# Mosfets.net
KiCad netlist of a schematic drawn in Altium Designer
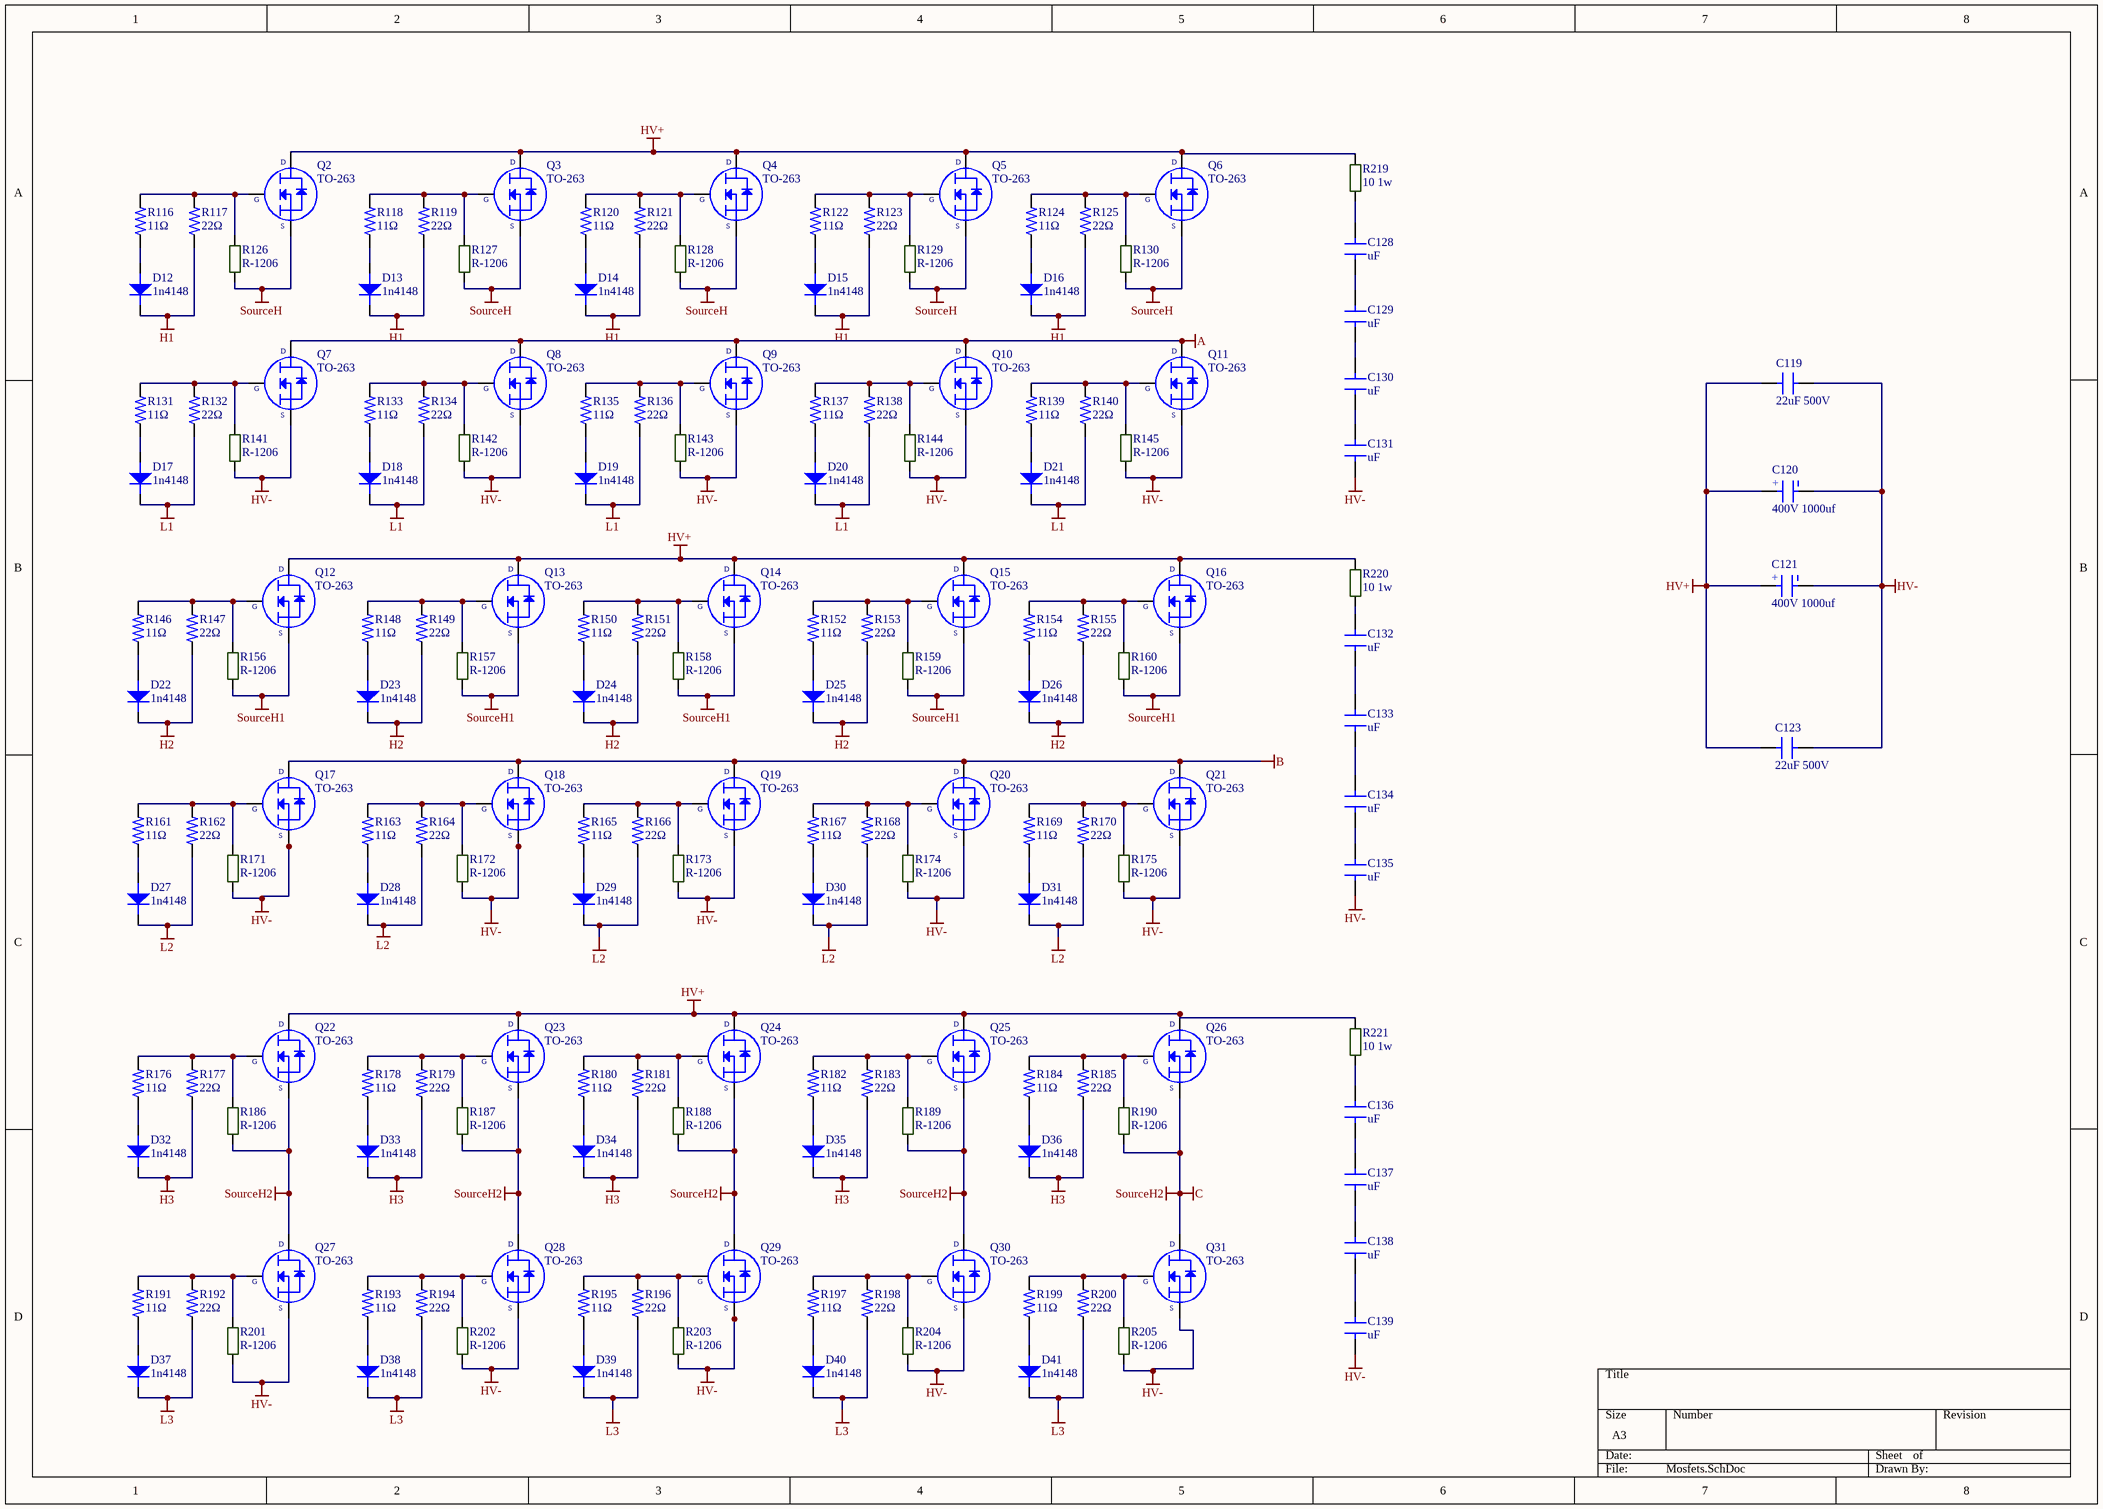
[diagram p0: Mosfets.SchDoc]

(export (version "E")
  (design (tool "Eeschema 10.0.6"))
  (components
    (comp (ref "C119")
      (value "22uF 500V")
      (footprint "CAP.POL 22UF 500VDC - duplicate")
      (libsource (lib "Gate Driver Board") (part "CAP.POL 22UF 500VDC"))
    )
    (comp (ref "C120")
      (value "400V 1000uf")
      (footprint "Koshin 63v 4700 cap")
      (fields
        (field (name "MANUFACTURER") "Nichicon")
        (field (name "MANUFACTURER PART NUMBER") "LKS1J472MESZ")
        (field (name "TOLERANCE") "20%")
      )
      (libsource (lib "Gate Driver Board") (part "Aluminum Electrolytic Capacitors"))
    )
    (comp (ref "C121")
      (value "400V 1000uf")
      (footprint "Koshin 63v 4700 cap")
      (fields
        (field (name "MANUFACTURER") "Nichicon")
        (field (name "MANUFACTURER PART NUMBER") "LKS1J472MESZ")
        (field (name "TOLERANCE") "20%")
      )
      (libsource (lib "Gate Driver Board") (part "Aluminum Electrolytic Capacitors"))
    )
    (comp (ref "C123")
      (value "22uF 500V")
      (footprint "CAP.POL 22UF 500VDC - duplicate")
      (libsource (lib "Gate Driver Board") (part "CAP.POL 22UF 500VDC"))
    )
    (comp (ref "C128")
      (value "uF")
      (footprint "C-1206")
      (libsource (lib "Gate Driver Board") (part "C-1206"))
    )
    (comp (ref "C129")
      (value "uF")
      (footprint "C-1206")
      (libsource (lib "Gate Driver Board") (part "C-1206"))
    )
    (comp (ref "C130")
      (value "uF")
      (footprint "C-1206")
      (libsource (lib "Gate Driver Board") (part "C-1206"))
    )
    (comp (ref "C131")
      (value "uF")
      (footprint "C-1206")
      (libsource (lib "Gate Driver Board") (part "C-1206"))
    )
    (comp (ref "C132")
      (value "uF")
      (footprint "C-1206")
      (libsource (lib "Gate Driver Board") (part "C-1206"))
    )
    (comp (ref "C133")
      (value "uF")
      (footprint "C-1206")
      (libsource (lib "Gate Driver Board") (part "C-1206"))
    )
    (comp (ref "C134")
      (value "uF")
      (footprint "C-1206")
      (libsource (lib "Gate Driver Board") (part "C-1206"))
    )
    (comp (ref "C135")
      (value "uF")
      (footprint "C-1206")
      (libsource (lib "Gate Driver Board") (part "C-1206"))
    )
    (comp (ref "C136")
      (value "uF")
      (footprint "C-1206")
      (libsource (lib "Gate Driver Board") (part "C-1206"))
    )
    (comp (ref "C137")
      (value "uF")
      (footprint "C-1206")
      (libsource (lib "Gate Driver Board") (part "C-1206"))
    )
    (comp (ref "C138")
      (value "uF")
      (footprint "C-1206")
      (libsource (lib "Gate Driver Board") (part "C-1206"))
    )
    (comp (ref "C139")
      (value "uF")
      (footprint "C-1206")
      (libsource (lib "Gate Driver Board") (part "C-1206"))
    )
    (comp (ref "D12")
      (value "1n4148")
      (footprint "LFI Power Board PcbLib1:SOD123")
      (description "Diode Small Signal Switching 100V 0.15A 2-Pin SOD-123 T/R")
      (fields
        (field (name "MANUFACTURER") "Vishay")
        (field (name "MANUFACTURER PART NUMBER") "1N4148W-E3-18")
      )
      (libsource (lib "Gate Driver Board") (part "1N4148W-E3-18"))
    )
    (comp (ref "D13")
      (value "1n4148")
      (footprint "LFI Power Board PcbLib1:SOD123")
      (description "Diode Small Signal Switching 100V 0.15A 2-Pin SOD-123 T/R")
      (fields
        (field (name "MANUFACTURER") "Vishay")
        (field (name "MANUFACTURER PART NUMBER") "1N4148W-E3-18")
      )
      (libsource (lib "Gate Driver Board") (part "1N4148W-E3-18"))
    )
    (comp (ref "D14")
      (value "1n4148")
      (footprint "LFI Power Board PcbLib1:SOD123")
      (description "Diode Small Signal Switching 100V 0.15A 2-Pin SOD-123 T/R")
      (fields
        (field (name "MANUFACTURER") "Vishay")
        (field (name "MANUFACTURER PART NUMBER") "1N4148W-E3-18")
      )
      (libsource (lib "Gate Driver Board") (part "1N4148W-E3-18"))
    )
    (comp (ref "D15")
      (value "1n4148")
      (footprint "LFI Power Board PcbLib1:SOD123")
      (description "Diode Small Signal Switching 100V 0.15A 2-Pin SOD-123 T/R")
      (fields
        (field (name "MANUFACTURER") "Vishay")
        (field (name "MANUFACTURER PART NUMBER") "1N4148W-E3-18")
      )
      (libsource (lib "Gate Driver Board") (part "1N4148W-E3-18"))
    )
    (comp (ref "D16")
      (value "1n4148")
      (footprint "LFI Power Board PcbLib1:SOD123")
      (description "Diode Small Signal Switching 100V 0.15A 2-Pin SOD-123 T/R")
      (fields
        (field (name "MANUFACTURER") "Vishay")
        (field (name "MANUFACTURER PART NUMBER") "1N4148W-E3-18")
      )
      (libsource (lib "Gate Driver Board") (part "1N4148W-E3-18"))
    )
    (comp (ref "D17")
      (value "1n4148")
      (footprint "LFI Power Board PcbLib1:SOD123")
      (description "Diode Small Signal Switching 100V 0.15A 2-Pin SOD-123 T/R")
      (fields
        (field (name "MANUFACTURER") "Vishay")
        (field (name "MANUFACTURER PART NUMBER") "1N4148W-E3-18")
      )
      (libsource (lib "Gate Driver Board") (part "1N4148W-E3-18"))
    )
    (comp (ref "D18")
      (value "1n4148")
      (footprint "LFI Power Board PcbLib1:SOD123")
      (description "Diode Small Signal Switching 100V 0.15A 2-Pin SOD-123 T/R")
      (fields
        (field (name "MANUFACTURER") "Vishay")
        (field (name "MANUFACTURER PART NUMBER") "1N4148W-E3-18")
      )
      (libsource (lib "Gate Driver Board") (part "1N4148W-E3-18"))
    )
    (comp (ref "D19")
      (value "1n4148")
      (footprint "LFI Power Board PcbLib1:SOD123")
      (description "Diode Small Signal Switching 100V 0.15A 2-Pin SOD-123 T/R")
      (fields
        (field (name "MANUFACTURER") "Vishay")
        (field (name "MANUFACTURER PART NUMBER") "1N4148W-E3-18")
      )
      (libsource (lib "Gate Driver Board") (part "1N4148W-E3-18"))
    )
    (comp (ref "D20")
      (value "1n4148")
      (footprint "LFI Power Board PcbLib1:SOD123")
      (description "Diode Small Signal Switching 100V 0.15A 2-Pin SOD-123 T/R")
      (fields
        (field (name "MANUFACTURER") "Vishay")
        (field (name "MANUFACTURER PART NUMBER") "1N4148W-E3-18")
      )
      (libsource (lib "Gate Driver Board") (part "1N4148W-E3-18"))
    )
    (comp (ref "D21")
      (value "1n4148")
      (footprint "LFI Power Board PcbLib1:SOD123")
      (description "Diode Small Signal Switching 100V 0.15A 2-Pin SOD-123 T/R")
      (fields
        (field (name "MANUFACTURER") "Vishay")
        (field (name "MANUFACTURER PART NUMBER") "1N4148W-E3-18")
      )
      (libsource (lib "Gate Driver Board") (part "1N4148W-E3-18"))
    )
    (comp (ref "D22")
      (value "1n4148")
      (footprint "LFI Power Board PcbLib1:SOD123")
      (description "Diode Small Signal Switching 100V 0.15A 2-Pin SOD-123 T/R")
      (fields
        (field (name "MANUFACTURER") "Vishay")
        (field (name "MANUFACTURER PART NUMBER") "1N4148W-E3-18")
      )
      (libsource (lib "Gate Driver Board") (part "1N4148W-E3-18"))
    )
    (comp (ref "D23")
      (value "1n4148")
      (footprint "LFI Power Board PcbLib1:SOD123")
      (description "Diode Small Signal Switching 100V 0.15A 2-Pin SOD-123 T/R")
      (fields
        (field (name "MANUFACTURER") "Vishay")
        (field (name "MANUFACTURER PART NUMBER") "1N4148W-E3-18")
      )
      (libsource (lib "Gate Driver Board") (part "1N4148W-E3-18"))
    )
    (comp (ref "D24")
      (value "1n4148")
      (footprint "LFI Power Board PcbLib1:SOD123")
      (description "Diode Small Signal Switching 100V 0.15A 2-Pin SOD-123 T/R")
      (fields
        (field (name "MANUFACTURER") "Vishay")
        (field (name "MANUFACTURER PART NUMBER") "1N4148W-E3-18")
      )
      (libsource (lib "Gate Driver Board") (part "1N4148W-E3-18"))
    )
    (comp (ref "D25")
      (value "1n4148")
      (footprint "LFI Power Board PcbLib1:SOD123")
      (description "Diode Small Signal Switching 100V 0.15A 2-Pin SOD-123 T/R")
      (fields
        (field (name "MANUFACTURER") "Vishay")
        (field (name "MANUFACTURER PART NUMBER") "1N4148W-E3-18")
      )
      (libsource (lib "Gate Driver Board") (part "1N4148W-E3-18"))
    )
    (comp (ref "D26")
      (value "1n4148")
      (footprint "LFI Power Board PcbLib1:SOD123")
      (description "Diode Small Signal Switching 100V 0.15A 2-Pin SOD-123 T/R")
      (fields
        (field (name "MANUFACTURER") "Vishay")
        (field (name "MANUFACTURER PART NUMBER") "1N4148W-E3-18")
      )
      (libsource (lib "Gate Driver Board") (part "1N4148W-E3-18"))
    )
    (comp (ref "D27")
      (value "1n4148")
      (footprint "LFI Power Board PcbLib1:SOD123")
      (description "Diode Small Signal Switching 100V 0.15A 2-Pin SOD-123 T/R")
      (fields
        (field (name "MANUFACTURER") "Vishay")
        (field (name "MANUFACTURER PART NUMBER") "1N4148W-E3-18")
      )
      (libsource (lib "Gate Driver Board") (part "1N4148W-E3-18"))
    )
    (comp (ref "D28")
      (value "1n4148")
      (footprint "LFI Power Board PcbLib1:SOD123")
      (description "Diode Small Signal Switching 100V 0.15A 2-Pin SOD-123 T/R")
      (fields
        (field (name "MANUFACTURER") "Vishay")
        (field (name "MANUFACTURER PART NUMBER") "1N4148W-E3-18")
      )
      (libsource (lib "Gate Driver Board") (part "1N4148W-E3-18"))
    )
    (comp (ref "D29")
      (value "1n4148")
      (footprint "LFI Power Board PcbLib1:SOD123")
      (description "Diode Small Signal Switching 100V 0.15A 2-Pin SOD-123 T/R")
      (fields
        (field (name "MANUFACTURER") "Vishay")
        (field (name "MANUFACTURER PART NUMBER") "1N4148W-E3-18")
      )
      (libsource (lib "Gate Driver Board") (part "1N4148W-E3-18"))
    )
    (comp (ref "D30")
      (value "1n4148")
      (footprint "LFI Power Board PcbLib1:SOD123")
      (description "Diode Small Signal Switching 100V 0.15A 2-Pin SOD-123 T/R")
      (fields
        (field (name "MANUFACTURER") "Vishay")
        (field (name "MANUFACTURER PART NUMBER") "1N4148W-E3-18")
      )
      (libsource (lib "Gate Driver Board") (part "1N4148W-E3-18"))
    )
    (comp (ref "D31")
      (value "1n4148")
      (footprint "LFI Power Board PcbLib1:SOD123")
      (description "Diode Small Signal Switching 100V 0.15A 2-Pin SOD-123 T/R")
      (fields
        (field (name "MANUFACTURER") "Vishay")
        (field (name "MANUFACTURER PART NUMBER") "1N4148W-E3-18")
      )
      (libsource (lib "Gate Driver Board") (part "1N4148W-E3-18"))
    )
    (comp (ref "D32")
      (value "1n4148")
      (footprint "LFI Power Board PcbLib1:SOD123")
      (description "Diode Small Signal Switching 100V 0.15A 2-Pin SOD-123 T/R")
      (fields
        (field (name "MANUFACTURER") "Vishay")
        (field (name "MANUFACTURER PART NUMBER") "1N4148W-E3-18")
      )
      (libsource (lib "Gate Driver Board") (part "1N4148W-E3-18"))
    )
    (comp (ref "D33")
      (value "1n4148")
      (footprint "LFI Power Board PcbLib1:SOD123")
      (description "Diode Small Signal Switching 100V 0.15A 2-Pin SOD-123 T/R")
      (fields
        (field (name "MANUFACTURER") "Vishay")
        (field (name "MANUFACTURER PART NUMBER") "1N4148W-E3-18")
      )
      (libsource (lib "Gate Driver Board") (part "1N4148W-E3-18"))
    )
    (comp (ref "D34")
      (value "1n4148")
      (footprint "LFI Power Board PcbLib1:SOD123")
      (description "Diode Small Signal Switching 100V 0.15A 2-Pin SOD-123 T/R")
      (fields
        (field (name "MANUFACTURER") "Vishay")
        (field (name "MANUFACTURER PART NUMBER") "1N4148W-E3-18")
      )
      (libsource (lib "Gate Driver Board") (part "1N4148W-E3-18"))
    )
    (comp (ref "D35")
      (value "1n4148")
      (footprint "LFI Power Board PcbLib1:SOD123")
      (description "Diode Small Signal Switching 100V 0.15A 2-Pin SOD-123 T/R")
      (fields
        (field (name "MANUFACTURER") "Vishay")
        (field (name "MANUFACTURER PART NUMBER") "1N4148W-E3-18")
      )
      (libsource (lib "Gate Driver Board") (part "1N4148W-E3-18"))
    )
    (comp (ref "D36")
      (value "1n4148")
      (footprint "LFI Power Board PcbLib1:SOD123")
      (description "Diode Small Signal Switching 100V 0.15A 2-Pin SOD-123 T/R")
      (fields
        (field (name "MANUFACTURER") "Vishay")
        (field (name "MANUFACTURER PART NUMBER") "1N4148W-E3-18")
      )
      (libsource (lib "Gate Driver Board") (part "1N4148W-E3-18"))
    )
    (comp (ref "D37")
      (value "1n4148")
      (footprint "LFI Power Board PcbLib1:SOD123")
      (description "Diode Small Signal Switching 100V 0.15A 2-Pin SOD-123 T/R")
      (fields
        (field (name "MANUFACTURER") "Vishay")
        (field (name "MANUFACTURER PART NUMBER") "1N4148W-E3-18")
      )
      (libsource (lib "Gate Driver Board") (part "1N4148W-E3-18"))
    )
    (comp (ref "D38")
      (value "1n4148")
      (footprint "LFI Power Board PcbLib1:SOD123")
      (description "Diode Small Signal Switching 100V 0.15A 2-Pin SOD-123 T/R")
      (fields
        (field (name "MANUFACTURER") "Vishay")
        (field (name "MANUFACTURER PART NUMBER") "1N4148W-E3-18")
      )
      (libsource (lib "Gate Driver Board") (part "1N4148W-E3-18"))
    )
    (comp (ref "D39")
      (value "1n4148")
      (footprint "LFI Power Board PcbLib1:SOD123")
      (description "Diode Small Signal Switching 100V 0.15A 2-Pin SOD-123 T/R")
      (fields
        (field (name "MANUFACTURER") "Vishay")
        (field (name "MANUFACTURER PART NUMBER") "1N4148W-E3-18")
      )
      (libsource (lib "Gate Driver Board") (part "1N4148W-E3-18"))
    )
    (comp (ref "D40")
      (value "1n4148")
      (footprint "LFI Power Board PcbLib1:SOD123")
      (description "Diode Small Signal Switching 100V 0.15A 2-Pin SOD-123 T/R")
      (fields
        (field (name "MANUFACTURER") "Vishay")
        (field (name "MANUFACTURER PART NUMBER") "1N4148W-E3-18")
      )
      (libsource (lib "Gate Driver Board") (part "1N4148W-E3-18"))
    )
    (comp (ref "D41")
      (value "1n4148")
      (footprint "LFI Power Board PcbLib1:SOD123")
      (description "Diode Small Signal Switching 100V 0.15A 2-Pin SOD-123 T/R")
      (fields
        (field (name "MANUFACTURER") "Vishay")
        (field (name "MANUFACTURER PART NUMBER") "1N4148W-E3-18")
      )
      (libsource (lib "Gate Driver Board") (part "1N4148W-E3-18"))
    )
    (comp (ref "Q2")
      (value "TO-263")
      (footprint "DPAK_TO263")
      (libsource (lib "Gate Driver Board") (part "TO-263"))
    )
    (comp (ref "Q3")
      (value "TO-263")
      (footprint "DPAK_TO263")
      (libsource (lib "Gate Driver Board") (part "TO-263"))
    )
    (comp (ref "Q4")
      (value "TO-263")
      (footprint "DPAK_TO263")
      (libsource (lib "Gate Driver Board") (part "TO-263"))
    )
    (comp (ref "Q5")
      (value "TO-263")
      (footprint "DPAK_TO263")
      (libsource (lib "Gate Driver Board") (part "TO-263"))
    )
    (comp (ref "Q6")
      (value "TO-263")
      (footprint "DPAK_TO263")
      (libsource (lib "Gate Driver Board") (part "TO-263"))
    )
    (comp (ref "Q7")
      (value "TO-263")
      (footprint "DPAK_TO263")
      (libsource (lib "Gate Driver Board") (part "TO-263"))
    )
    (comp (ref "Q8")
      (value "TO-263")
      (footprint "DPAK_TO263")
      (libsource (lib "Gate Driver Board") (part "TO-263"))
    )
    (comp (ref "Q9")
      (value "TO-263")
      (footprint "DPAK_TO263")
      (libsource (lib "Gate Driver Board") (part "TO-263"))
    )
    (comp (ref "Q10")
      (value "TO-263")
      (footprint "DPAK_TO263")
      (libsource (lib "Gate Driver Board") (part "TO-263"))
    )
    (comp (ref "Q11")
      (value "TO-263")
      (footprint "DPAK_TO263")
      (libsource (lib "Gate Driver Board") (part "TO-263"))
    )
    (comp (ref "Q12")
      (value "TO-263")
      (footprint "DPAK_TO263")
      (libsource (lib "Gate Driver Board") (part "TO-263"))
    )
    (comp (ref "Q13")
      (value "TO-263")
      (footprint "DPAK_TO263")
      (libsource (lib "Gate Driver Board") (part "TO-263"))
    )
    (comp (ref "Q14")
      (value "TO-263")
      (footprint "DPAK_TO263")
      (libsource (lib "Gate Driver Board") (part "TO-263"))
    )
    (comp (ref "Q15")
      (value "TO-263")
      (footprint "DPAK_TO263")
      (libsource (lib "Gate Driver Board") (part "TO-263"))
    )
    (comp (ref "Q16")
      (value "TO-263")
      (footprint "DPAK_TO263")
      (libsource (lib "Gate Driver Board") (part "TO-263"))
    )
    (comp (ref "Q17")
      (value "TO-263")
      (footprint "DPAK_TO263")
      (libsource (lib "Gate Driver Board") (part "TO-263"))
    )
    (comp (ref "Q18")
      (value "TO-263")
      (footprint "DPAK_TO263")
      (libsource (lib "Gate Driver Board") (part "TO-263"))
    )
    (comp (ref "Q19")
      (value "TO-263")
      (footprint "DPAK_TO263")
      (libsource (lib "Gate Driver Board") (part "TO-263"))
    )
    (comp (ref "Q20")
      (value "TO-263")
      (footprint "DPAK_TO263")
      (libsource (lib "Gate Driver Board") (part "TO-263"))
    )
    (comp (ref "Q21")
      (value "TO-263")
      (footprint "DPAK_TO263")
      (libsource (lib "Gate Driver Board") (part "TO-263"))
    )
    (comp (ref "Q22")
      (value "TO-263")
      (footprint "DPAK_TO263")
      (libsource (lib "Gate Driver Board") (part "TO-263"))
    )
    (comp (ref "Q23")
      (value "TO-263")
      (footprint "DPAK_TO263")
      (libsource (lib "Gate Driver Board") (part "TO-263"))
    )
    (comp (ref "Q24")
      (value "TO-263")
      (footprint "DPAK_TO263")
      (libsource (lib "Gate Driver Board") (part "TO-263"))
    )
    (comp (ref "Q25")
      (value "TO-263")
      (footprint "DPAK_TO263")
      (libsource (lib "Gate Driver Board") (part "TO-263"))
    )
    (comp (ref "Q26")
      (value "TO-263")
      (footprint "DPAK_TO263")
      (libsource (lib "Gate Driver Board") (part "TO-263"))
    )
    (comp (ref "Q27")
      (value "TO-263")
      (footprint "DPAK_TO263")
      (libsource (lib "Gate Driver Board") (part "TO-263"))
    )
    (comp (ref "Q28")
      (value "TO-263")
      (footprint "DPAK_TO263")
      (libsource (lib "Gate Driver Board") (part "TO-263"))
    )
    (comp (ref "Q29")
      (value "TO-263")
      (footprint "DPAK_TO263")
      (libsource (lib "Gate Driver Board") (part "TO-263"))
    )
    (comp (ref "Q30")
      (value "TO-263")
      (footprint "DPAK_TO263")
      (libsource (lib "Gate Driver Board") (part "TO-263"))
    )
    (comp (ref "Q31")
      (value "TO-263")
      (footprint "DPAK_TO263")
      (libsource (lib "Gate Driver Board") (part "TO-263"))
    )
    (comp (ref "R116")
      (value "11Ω")
      (footprint "R-1206W")
      (description "CRG1206 1% 11R")
      (fields (field (name "MP") "1623463-1"))
      (libsource (lib "Gate Driver Board") (part "RES 11Ω 1206"))
    )
    (comp (ref "R117")
      (value "22Ω")
      (footprint "R-1206W")
      (description "CRG1206 1% 22R")
      (fields (field (name "MP") "1623463-1"))
      (libsource (lib "Gate Driver Board") (part "RES 22Ω 1206"))
    )
    (comp (ref "R118")
      (value "11Ω")
      (footprint "R-1206W")
      (description "CRG1206 1% 11R")
      (fields (field (name "MP") "1623463-1"))
      (libsource (lib "Gate Driver Board") (part "RES 11Ω 1206"))
    )
    (comp (ref "R119")
      (value "22Ω")
      (footprint "R-1206W")
      (description "CRG1206 1% 22R")
      (fields (field (name "MP") "1623463-1"))
      (libsource (lib "Gate Driver Board") (part "RES 22Ω 1206"))
    )
    (comp (ref "R120")
      (value "11Ω")
      (footprint "R-1206W")
      (description "CRG1206 1% 11R")
      (fields (field (name "MP") "1623463-1"))
      (libsource (lib "Gate Driver Board") (part "RES 11Ω 1206"))
    )
    (comp (ref "R121")
      (value "22Ω")
      (footprint "R-1206W")
      (description "CRG1206 1% 22R")
      (fields (field (name "MP") "1623463-1"))
      (libsource (lib "Gate Driver Board") (part "RES 22Ω 1206"))
    )
    (comp (ref "R122")
      (value "11Ω")
      (footprint "R-1206W")
      (description "CRG1206 1% 11R")
      (fields (field (name "MP") "1623463-1"))
      (libsource (lib "Gate Driver Board") (part "RES 11Ω 1206"))
    )
    (comp (ref "R123")
      (value "22Ω")
      (footprint "R-1206W")
      (description "CRG1206 1% 22R")
      (fields (field (name "MP") "1623463-1"))
      (libsource (lib "Gate Driver Board") (part "RES 22Ω 1206"))
    )
    (comp (ref "R124")
      (value "11Ω")
      (footprint "R-1206W")
      (description "CRG1206 1% 11R")
      (fields (field (name "MP") "1623463-1"))
      (libsource (lib "Gate Driver Board") (part "RES 11Ω 1206"))
    )
    (comp (ref "R125")
      (value "22Ω")
      (footprint "R-1206W")
      (description "CRG1206 1% 22R")
      (fields (field (name "MP") "1623463-1"))
      (libsource (lib "Gate Driver Board") (part "RES 22Ω 1206"))
    )
    (comp (ref "R126")
      (value "R-1206")
      (footprint "R-1206")
      (description "Res1206")
      (libsource (lib "Gate Driver Board") (part "R-1206"))
    )
    (comp (ref "R127")
      (value "R-1206")
      (footprint "R-1206")
      (description "Res1206")
      (libsource (lib "Gate Driver Board") (part "R-1206"))
    )
    (comp (ref "R128")
      (value "R-1206")
      (footprint "R-1206")
      (description "Res1206")
      (libsource (lib "Gate Driver Board") (part "R-1206"))
    )
    (comp (ref "R129")
      (value "R-1206")
      (footprint "R-1206")
      (description "Res1206")
      (libsource (lib "Gate Driver Board") (part "R-1206"))
    )
    (comp (ref "R130")
      (value "R-1206")
      (footprint "R-1206")
      (description "Res1206")
      (libsource (lib "Gate Driver Board") (part "R-1206"))
    )
    (comp (ref "R131")
      (value "11Ω")
      (footprint "R-1206W")
      (description "CRG1206 1% 11R")
      (fields (field (name "MP") "1623463-1"))
      (libsource (lib "Gate Driver Board") (part "RES 11Ω 1206"))
    )
    (comp (ref "R132")
      (value "22Ω")
      (footprint "R-1206W")
      (description "CRG1206 1% 22R")
      (fields (field (name "MP") "1623463-1"))
      (libsource (lib "Gate Driver Board") (part "RES 22Ω 1206"))
    )
    (comp (ref "R133")
      (value "11Ω")
      (footprint "R-1206W")
      (description "CRG1206 1% 11R")
      (fields (field (name "MP") "1623463-1"))
      (libsource (lib "Gate Driver Board") (part "RES 11Ω 1206"))
    )
    (comp (ref "R134")
      (value "22Ω")
      (footprint "R-1206W")
      (description "CRG1206 1% 22R")
      (fields (field (name "MP") "1623463-1"))
      (libsource (lib "Gate Driver Board") (part "RES 22Ω 1206"))
    )
    (comp (ref "R135")
      (value "11Ω")
      (footprint "R-1206W")
      (description "CRG1206 1% 11R")
      (fields (field (name "MP") "1623463-1"))
      (libsource (lib "Gate Driver Board") (part "RES 11Ω 1206"))
    )
    (comp (ref "R136")
      (value "22Ω")
      (footprint "R-1206W")
      (description "CRG1206 1% 22R")
      (fields (field (name "MP") "1623463-1"))
      (libsource (lib "Gate Driver Board") (part "RES 22Ω 1206"))
    )
    (comp (ref "R137")
      (value "11Ω")
      (footprint "R-1206W")
      (description "CRG1206 1% 11R")
      (fields (field (name "MP") "1623463-1"))
      (libsource (lib "Gate Driver Board") (part "RES 11Ω 1206"))
    )
    (comp (ref "R138")
      (value "22Ω")
      (footprint "R-1206W")
      (description "CRG1206 1% 22R")
      (fields (field (name "MP") "1623463-1"))
      (libsource (lib "Gate Driver Board") (part "RES 22Ω 1206"))
    )
    (comp (ref "R139")
      (value "11Ω")
      (footprint "R-1206W")
      (description "CRG1206 1% 11R")
      (fields (field (name "MP") "1623463-1"))
      (libsource (lib "Gate Driver Board") (part "RES 11Ω 1206"))
    )
    (comp (ref "R140")
      (value "22Ω")
      (footprint "R-1206W")
      (description "CRG1206 1% 22R")
      (fields (field (name "MP") "1623463-1"))
      (libsource (lib "Gate Driver Board") (part "RES 22Ω 1206"))
    )
    (comp (ref "R141")
      (value "R-1206")
      (footprint "R-1206")
      (description "Res1206")
      (libsource (lib "Gate Driver Board") (part "R-1206"))
    )
    (comp (ref "R142")
      (value "R-1206")
      (footprint "R-1206")
      (description "Res1206")
      (libsource (lib "Gate Driver Board") (part "R-1206"))
    )
    (comp (ref "R143")
      (value "R-1206")
      (footprint "R-1206")
      (description "Res1206")
      (libsource (lib "Gate Driver Board") (part "R-1206"))
    )
    (comp (ref "R144")
      (value "R-1206")
      (footprint "R-1206")
      (description "Res1206")
      (libsource (lib "Gate Driver Board") (part "R-1206"))
    )
    (comp (ref "R145")
      (value "R-1206")
      (footprint "R-1206")
      (description "Res1206")
      (libsource (lib "Gate Driver Board") (part "R-1206"))
    )
    (comp (ref "R146")
      (value "11Ω")
      (footprint "R-1206W")
      (description "CRG1206 1% 11R")
      (fields (field (name "MP") "1623463-1"))
      (libsource (lib "Gate Driver Board") (part "RES 11Ω 1206"))
    )
    (comp (ref "R147")
      (value "22Ω")
      (footprint "R-1206W")
      (description "CRG1206 1% 22R")
      (fields (field (name "MP") "1623463-1"))
      (libsource (lib "Gate Driver Board") (part "RES 22Ω 1206"))
    )
    (comp (ref "R148")
      (value "11Ω")
      (footprint "R-1206W")
      (description "CRG1206 1% 11R")
      (fields (field (name "MP") "1623463-1"))
      (libsource (lib "Gate Driver Board") (part "RES 11Ω 1206"))
    )
    (comp (ref "R149")
      (value "22Ω")
      (footprint "R-1206W")
      (description "CRG1206 1% 22R")
      (fields (field (name "MP") "1623463-1"))
      (libsource (lib "Gate Driver Board") (part "RES 22Ω 1206"))
    )
    (comp (ref "R150")
      (value "11Ω")
      (footprint "R-1206W")
      (description "CRG1206 1% 11R")
      (fields (field (name "MP") "1623463-1"))
      (libsource (lib "Gate Driver Board") (part "RES 11Ω 1206"))
    )
    (comp (ref "R151")
      (value "22Ω")
      (footprint "R-1206W")
      (description "CRG1206 1% 22R")
      (fields (field (name "MP") "1623463-1"))
      (libsource (lib "Gate Driver Board") (part "RES 22Ω 1206"))
    )
    (comp (ref "R152")
      (value "11Ω")
      (footprint "R-1206W")
      (description "CRG1206 1% 11R")
      (fields (field (name "MP") "1623463-1"))
      (libsource (lib "Gate Driver Board") (part "RES 11Ω 1206"))
    )
    (comp (ref "R153")
      (value "22Ω")
      (footprint "R-1206W")
      (description "CRG1206 1% 22R")
      (fields (field (name "MP") "1623463-1"))
      (libsource (lib "Gate Driver Board") (part "RES 22Ω 1206"))
    )
    (comp (ref "R154")
      (value "11Ω")
      (footprint "R-1206W")
      (description "CRG1206 1% 11R")
      (fields (field (name "MP") "1623463-1"))
      (libsource (lib "Gate Driver Board") (part "RES 11Ω 1206"))
    )
    (comp (ref "R155")
      (value "22Ω")
      (footprint "R-1206W")
      (description "CRG1206 1% 22R")
      (fields (field (name "MP") "1623463-1"))
      (libsource (lib "Gate Driver Board") (part "RES 22Ω 1206"))
    )
    (comp (ref "R156")
      (value "R-1206")
      (footprint "R-1206")
      (description "Res1206")
      (libsource (lib "Gate Driver Board") (part "R-1206"))
    )
    (comp (ref "R157")
      (value "R-1206")
      (footprint "R-1206")
      (description "Res1206")
      (libsource (lib "Gate Driver Board") (part "R-1206"))
    )
    (comp (ref "R158")
      (value "R-1206")
      (footprint "R-1206")
      (description "Res1206")
      (libsource (lib "Gate Driver Board") (part "R-1206"))
    )
    (comp (ref "R159")
      (value "R-1206")
      (footprint "R-1206")
      (description "Res1206")
      (libsource (lib "Gate Driver Board") (part "R-1206"))
    )
    (comp (ref "R160")
      (value "R-1206")
      (footprint "R-1206")
      (description "Res1206")
      (libsource (lib "Gate Driver Board") (part "R-1206"))
    )
    (comp (ref "R161")
      (value "11Ω")
      (footprint "R-1206W")
      (description "CRG1206 1% 11R")
      (fields (field (name "MP") "1623463-1"))
      (libsource (lib "Gate Driver Board") (part "RES 11Ω 1206"))
    )
    (comp (ref "R162")
      (value "22Ω")
      (footprint "R-1206W")
      (description "CRG1206 1% 22R")
      (fields (field (name "MP") "1623463-1"))
      (libsource (lib "Gate Driver Board") (part "RES 22Ω 1206"))
    )
    (comp (ref "R163")
      (value "11Ω")
      (footprint "R-1206W")
      (description "CRG1206 1% 11R")
      (fields (field (name "MP") "1623463-1"))
      (libsource (lib "Gate Driver Board") (part "RES 11Ω 1206"))
    )
    (comp (ref "R164")
      (value "22Ω")
      (footprint "R-1206W")
      (description "CRG1206 1% 22R")
      (fields (field (name "MP") "1623463-1"))
      (libsource (lib "Gate Driver Board") (part "RES 22Ω 1206"))
    )
    (comp (ref "R165")
      (value "11Ω")
      (footprint "R-1206W")
      (description "CRG1206 1% 11R")
      (fields (field (name "MP") "1623463-1"))
      (libsource (lib "Gate Driver Board") (part "RES 11Ω 1206"))
    )
    (comp (ref "R166")
      (value "22Ω")
      (footprint "R-1206W")
      (description "CRG1206 1% 22R")
      (fields (field (name "MP") "1623463-1"))
      (libsource (lib "Gate Driver Board") (part "RES 22Ω 1206"))
    )
    (comp (ref "R167")
      (value "11Ω")
      (footprint "R-1206W")
      (description "CRG1206 1% 11R")
      (fields (field (name "MP") "1623463-1"))
      (libsource (lib "Gate Driver Board") (part "RES 11Ω 1206"))
    )
    (comp (ref "R168")
      (value "22Ω")
      (footprint "R-1206W")
      (description "CRG1206 1% 22R")
      (fields (field (name "MP") "1623463-1"))
      (libsource (lib "Gate Driver Board") (part "RES 22Ω 1206"))
    )
    (comp (ref "R169")
      (value "11Ω")
      (footprint "R-1206W")
      (description "CRG1206 1% 11R")
      (fields (field (name "MP") "1623463-1"))
      (libsource (lib "Gate Driver Board") (part "RES 11Ω 1206"))
    )
    (comp (ref "R170")
      (value "22Ω")
      (footprint "R-1206W")
      (description "CRG1206 1% 22R")
      (fields (field (name "MP") "1623463-1"))
      (libsource (lib "Gate Driver Board") (part "RES 22Ω 1206"))
    )
    (comp (ref "R171")
      (value "R-1206")
      (footprint "R-1206")
      (description "Res1206")
      (libsource (lib "Gate Driver Board") (part "R-1206"))
    )
    (comp (ref "R172")
      (value "R-1206")
      (footprint "R-1206")
      (description "Res1206")
      (libsource (lib "Gate Driver Board") (part "R-1206"))
    )
    (comp (ref "R173")
      (value "R-1206")
      (footprint "R-1206")
      (description "Res1206")
      (libsource (lib "Gate Driver Board") (part "R-1206"))
    )
    (comp (ref "R174")
      (value "R-1206")
      (footprint "R-1206")
      (description "Res1206")
      (libsource (lib "Gate Driver Board") (part "R-1206"))
    )
    (comp (ref "R175")
      (value "R-1206")
      (footprint "R-1206")
      (description "Res1206")
      (libsource (lib "Gate Driver Board") (part "R-1206"))
    )
    (comp (ref "R176")
      (value "11Ω")
      (footprint "R-1206W")
      (description "CRG1206 1% 11R")
      (fields (field (name "MP") "1623463-1"))
      (libsource (lib "Gate Driver Board") (part "RES 11Ω 1206"))
    )
    (comp (ref "R177")
      (value "22Ω")
      (footprint "R-1206W")
      (description "CRG1206 1% 22R")
      (fields (field (name "MP") "1623463-1"))
      (libsource (lib "Gate Driver Board") (part "RES 22Ω 1206"))
    )
    (comp (ref "R178")
      (value "11Ω")
      (footprint "R-1206W")
      (description "CRG1206 1% 11R")
      (fields (field (name "MP") "1623463-1"))
      (libsource (lib "Gate Driver Board") (part "RES 11Ω 1206"))
    )
    (comp (ref "R179")
      (value "22Ω")
      (footprint "R-1206W")
      (description "CRG1206 1% 22R")
      (fields (field (name "MP") "1623463-1"))
      (libsource (lib "Gate Driver Board") (part "RES 22Ω 1206"))
    )
    (comp (ref "R180")
      (value "11Ω")
      (footprint "R-1206W")
      (description "CRG1206 1% 11R")
      (fields (field (name "MP") "1623463-1"))
      (libsource (lib "Gate Driver Board") (part "RES 11Ω 1206"))
    )
    (comp (ref "R181")
      (value "22Ω")
      (footprint "R-1206W")
      (description "CRG1206 1% 22R")
      (fields (field (name "MP") "1623463-1"))
      (libsource (lib "Gate Driver Board") (part "RES 22Ω 1206"))
    )
    (comp (ref "R182")
      (value "11Ω")
      (footprint "R-1206W")
      (description "CRG1206 1% 11R")
      (fields (field (name "MP") "1623463-1"))
      (libsource (lib "Gate Driver Board") (part "RES 11Ω 1206"))
    )
    (comp (ref "R183")
      (value "22Ω")
      (footprint "R-1206W")
      (description "CRG1206 1% 22R")
      (fields (field (name "MP") "1623463-1"))
      (libsource (lib "Gate Driver Board") (part "RES 22Ω 1206"))
    )
    (comp (ref "R184")
      (value "11Ω")
      (footprint "R-1206W")
      (description "CRG1206 1% 11R")
      (fields (field (name "MP") "1623463-1"))
      (libsource (lib "Gate Driver Board") (part "RES 11Ω 1206"))
    )
    (comp (ref "R185")
      (value "22Ω")
      (footprint "R-1206W")
      (description "CRG1206 1% 22R")
      (fields (field (name "MP") "1623463-1"))
      (libsource (lib "Gate Driver Board") (part "RES 22Ω 1206"))
    )
    (comp (ref "R186")
      (value "R-1206")
      (footprint "R-1206")
      (description "Res1206")
      (libsource (lib "Gate Driver Board") (part "R-1206"))
    )
    (comp (ref "R187")
      (value "R-1206")
      (footprint "R-1206")
      (description "Res1206")
      (libsource (lib "Gate Driver Board") (part "R-1206"))
    )
    (comp (ref "R188")
      (value "R-1206")
      (footprint "R-1206")
      (description "Res1206")
      (libsource (lib "Gate Driver Board") (part "R-1206"))
    )
    (comp (ref "R189")
      (value "R-1206")
      (footprint "R-1206")
      (description "Res1206")
      (libsource (lib "Gate Driver Board") (part "R-1206"))
    )
    (comp (ref "R190")
      (value "R-1206")
      (footprint "R-1206")
      (description "Res1206")
      (libsource (lib "Gate Driver Board") (part "R-1206"))
    )
    (comp (ref "R191")
      (value "11Ω")
      (footprint "R-1206W")
      (description "CRG1206 1% 11R")
      (fields (field (name "MP") "1623463-1"))
      (libsource (lib "Gate Driver Board") (part "RES 11Ω 1206"))
    )
    (comp (ref "R192")
      (value "22Ω")
      (footprint "R-1206W")
      (description "CRG1206 1% 22R")
      (fields (field (name "MP") "1623463-1"))
      (libsource (lib "Gate Driver Board") (part "RES 22Ω 1206"))
    )
    (comp (ref "R193")
      (value "11Ω")
      (footprint "R-1206W")
      (description "CRG1206 1% 11R")
      (fields (field (name "MP") "1623463-1"))
      (libsource (lib "Gate Driver Board") (part "RES 11Ω 1206"))
    )
    (comp (ref "R194")
      (value "22Ω")
      (footprint "R-1206W")
      (description "CRG1206 1% 22R")
      (fields (field (name "MP") "1623463-1"))
      (libsource (lib "Gate Driver Board") (part "RES 22Ω 1206"))
    )
    (comp (ref "R195")
      (value "11Ω")
      (footprint "R-1206W")
      (description "CRG1206 1% 11R")
      (fields (field (name "MP") "1623463-1"))
      (libsource (lib "Gate Driver Board") (part "RES 11Ω 1206"))
    )
    (comp (ref "R196")
      (value "22Ω")
      (footprint "R-1206W")
      (description "CRG1206 1% 22R")
      (fields (field (name "MP") "1623463-1"))
      (libsource (lib "Gate Driver Board") (part "RES 22Ω 1206"))
    )
    (comp (ref "R197")
      (value "11Ω")
      (footprint "R-1206W")
      (description "CRG1206 1% 11R")
      (fields (field (name "MP") "1623463-1"))
      (libsource (lib "Gate Driver Board") (part "RES 11Ω 1206"))
    )
    (comp (ref "R198")
      (value "22Ω")
      (footprint "R-1206W")
      (description "CRG1206 1% 22R")
      (fields (field (name "MP") "1623463-1"))
      (libsource (lib "Gate Driver Board") (part "RES 22Ω 1206"))
    )
    (comp (ref "R199")
      (value "11Ω")
      (footprint "R-1206W")
      (description "CRG1206 1% 11R")
      (fields (field (name "MP") "1623463-1"))
      (libsource (lib "Gate Driver Board") (part "RES 11Ω 1206"))
    )
    (comp (ref "R200")
      (value "22Ω")
      (footprint "R-1206W")
      (description "CRG1206 1% 22R")
      (fields (field (name "MP") "1623463-1"))
      (libsource (lib "Gate Driver Board") (part "RES 22Ω 1206"))
    )
    (comp (ref "R201")
      (value "R-1206")
      (footprint "R-1206")
      (description "Res1206")
      (libsource (lib "Gate Driver Board") (part "R-1206"))
    )
    (comp (ref "R202")
      (value "R-1206")
      (footprint "R-1206")
      (description "Res1206")
      (libsource (lib "Gate Driver Board") (part "R-1206"))
    )
    (comp (ref "R203")
      (value "R-1206")
      (footprint "R-1206")
      (description "Res1206")
      (libsource (lib "Gate Driver Board") (part "R-1206"))
    )
    (comp (ref "R204")
      (value "R-1206")
      (footprint "R-1206")
      (description "Res1206")
      (libsource (lib "Gate Driver Board") (part "R-1206"))
    )
    (comp (ref "R205")
      (value "R-1206")
      (footprint "R-1206")
      (description "Res1206")
      (libsource (lib "Gate Driver Board") (part "R-1206"))
    )
    (comp (ref "R219")
      (value "10 1w")
      (footprint "R-2512")
      (libsource (lib "Gate Driver Board") (part "R-2512"))
    )
    (comp (ref "R220")
      (value "10 1w")
      (footprint "R-2512")
      (libsource (lib "Gate Driver Board") (part "R-2512"))
    )
    (comp (ref "R221")
      (value "10 1w")
      (footprint "R-2512")
      (libsource (lib "Gate Driver Board") (part "R-2512"))
    )
  )
  (nets
    (net (code "1") (name "A") (class "Default")
      (node (ref "Q10") (pin "3") (pinfunction "3_3") (pintype "passive"))
      (node (ref "Q11") (pin "3") (pinfunction "3_3") (pintype "passive"))
      (node (ref "Q7") (pin "3") (pinfunction "3_3") (pintype "passive"))
      (node (ref "Q8") (pin "3") (pinfunction "3_3") (pintype "passive"))
      (node (ref "Q9") (pin "3") (pinfunction "3_3") (pintype "passive"))
    )
    (net (code "2") (name "B") (class "Default")
      (node (ref "Q17") (pin "3") (pinfunction "3_3") (pintype "passive"))
      (node (ref "Q18") (pin "3") (pinfunction "3_3") (pintype "passive"))
      (node (ref "Q19") (pin "3") (pinfunction "3_3") (pintype "passive"))
      (node (ref "Q20") (pin "3") (pinfunction "3_3") (pintype "passive"))
      (node (ref "Q21") (pin "3") (pinfunction "3_3") (pintype "passive"))
    )
    (net (code "3") (name "C") (class "Default")
      (node (ref "Q22") (pin "2") (pinfunction "2_2") (pintype "passive"))
      (node (ref "Q23") (pin "2") (pinfunction "2_2") (pintype "passive"))
      (node (ref "Q24") (pin "2") (pinfunction "2_2") (pintype "passive"))
      (node (ref "Q25") (pin "2") (pinfunction "2_2") (pintype "passive"))
      (node (ref "Q26") (pin "2") (pinfunction "2_2") (pintype "passive"))
      (node (ref "Q27") (pin "3") (pinfunction "3_3") (pintype "passive"))
      (node (ref "Q28") (pin "3") (pinfunction "3_3") (pintype "passive"))
      (node (ref "Q29") (pin "3") (pinfunction "3_3") (pintype "passive"))
      (node (ref "Q30") (pin "3") (pinfunction "3_3") (pintype "passive"))
      (node (ref "Q31") (pin "3") (pinfunction "3_3") (pintype "passive"))
      (node (ref "R186") (pin "1") (pinfunction "1_1") (pintype "passive"))
      (node (ref "R187") (pin "1") (pinfunction "1_1") (pintype "passive"))
      (node (ref "R188") (pin "1") (pinfunction "1_1") (pintype "passive"))
      (node (ref "R189") (pin "1") (pinfunction "1_1") (pintype "passive"))
      (node (ref "R190") (pin "1") (pinfunction "1_1") (pintype "passive"))
    )
    (net (code "4") (name "H1") (class "Default")
      (node (ref "D12") (pin "k") (pinfunction "k_k") (pintype "passive"))
      (node (ref "D13") (pin "k") (pinfunction "k_k") (pintype "passive"))
      (node (ref "D14") (pin "k") (pinfunction "k_k") (pintype "passive"))
      (node (ref "D15") (pin "k") (pinfunction "k_k") (pintype "passive"))
      (node (ref "D16") (pin "k") (pinfunction "k_k") (pintype "passive"))
      (node (ref "R117") (pin "1") (pinfunction "1_1") (pintype "passive"))
      (node (ref "R119") (pin "1") (pinfunction "1_1") (pintype "passive"))
      (node (ref "R121") (pin "1") (pinfunction "1_1") (pintype "passive"))
      (node (ref "R123") (pin "1") (pinfunction "1_1") (pintype "passive"))
      (node (ref "R125") (pin "1") (pinfunction "1_1") (pintype "passive"))
    )
    (net (code "5") (name "H2") (class "Default")
      (node (ref "D22") (pin "k") (pinfunction "k_k") (pintype "passive"))
      (node (ref "D23") (pin "k") (pinfunction "k_k") (pintype "passive"))
      (node (ref "D24") (pin "k") (pinfunction "k_k") (pintype "passive"))
      (node (ref "D25") (pin "k") (pinfunction "k_k") (pintype "passive"))
      (node (ref "D26") (pin "k") (pinfunction "k_k") (pintype "passive"))
      (node (ref "R147") (pin "1") (pinfunction "1_1") (pintype "passive"))
      (node (ref "R149") (pin "1") (pinfunction "1_1") (pintype "passive"))
      (node (ref "R151") (pin "1") (pinfunction "1_1") (pintype "passive"))
      (node (ref "R153") (pin "1") (pinfunction "1_1") (pintype "passive"))
      (node (ref "R155") (pin "1") (pinfunction "1_1") (pintype "passive"))
    )
    (net (code "6") (name "H3") (class "Default")
      (node (ref "D32") (pin "k") (pinfunction "k_k") (pintype "passive"))
      (node (ref "D33") (pin "k") (pinfunction "k_k") (pintype "passive"))
      (node (ref "D34") (pin "k") (pinfunction "k_k") (pintype "passive"))
      (node (ref "D35") (pin "k") (pinfunction "k_k") (pintype "passive"))
      (node (ref "D36") (pin "k") (pinfunction "k_k") (pintype "passive"))
      (node (ref "R177") (pin "1") (pinfunction "1_1") (pintype "passive"))
      (node (ref "R179") (pin "1") (pinfunction "1_1") (pintype "passive"))
      (node (ref "R181") (pin "1") (pinfunction "1_1") (pintype "passive"))
      (node (ref "R183") (pin "1") (pinfunction "1_1") (pintype "passive"))
      (node (ref "R185") (pin "1") (pinfunction "1_1") (pintype "passive"))
    )
    (net (code "7") (name "HV+") (class "Default")
      (node (ref "C119") (pin "1") (pinfunction "1_1") (pintype "passive"))
      (node (ref "C120") (pin "2") (pinfunction "2_2") (pintype "passive"))
      (node (ref "C121") (pin "2") (pinfunction "2_2") (pintype "passive"))
      (node (ref "C123") (pin "1") (pinfunction "1_1") (pintype "passive"))
      (node (ref "Q12") (pin "3") (pinfunction "3_3") (pintype "passive"))
      (node (ref "Q13") (pin "3") (pinfunction "3_3") (pintype "passive"))
      (node (ref "Q14") (pin "3") (pinfunction "3_3") (pintype "passive"))
      (node (ref "Q15") (pin "3") (pinfunction "3_3") (pintype "passive"))
      (node (ref "Q16") (pin "3") (pinfunction "3_3") (pintype "passive"))
      (node (ref "Q2") (pin "3") (pinfunction "3_3") (pintype "passive"))
      (node (ref "Q22") (pin "3") (pinfunction "3_3") (pintype "passive"))
      (node (ref "Q23") (pin "3") (pinfunction "3_3") (pintype "passive"))
      (node (ref "Q24") (pin "3") (pinfunction "3_3") (pintype "passive"))
      (node (ref "Q25") (pin "3") (pinfunction "3_3") (pintype "passive"))
      (node (ref "Q26") (pin "3") (pinfunction "3_3") (pintype "passive"))
      (node (ref "Q3") (pin "3") (pinfunction "3_3") (pintype "passive"))
      (node (ref "Q4") (pin "3") (pinfunction "3_3") (pintype "passive"))
      (node (ref "Q5") (pin "3") (pinfunction "3_3") (pintype "passive"))
      (node (ref "Q6") (pin "3") (pinfunction "3_3") (pintype "passive"))
      (node (ref "R219") (pin "2") (pinfunction "2_2") (pintype "passive"))
      (node (ref "R220") (pin "2") (pinfunction "2_2") (pintype "passive"))
      (node (ref "R221") (pin "2") (pinfunction "2_2") (pintype "passive"))
    )
    (net (code "8") (name "HV-") (class "Default")
      (node (ref "C119") (pin "2") (pinfunction "2_2") (pintype "passive"))
      (node (ref "C120") (pin "1") (pinfunction "1_1") (pintype "passive"))
      (node (ref "C121") (pin "1") (pinfunction "1_1") (pintype "passive"))
      (node (ref "C123") (pin "2") (pinfunction "2_2") (pintype "passive"))
      (node (ref "C135") (pin "1") (pinfunction "1_1") (pintype "passive"))
      (node (ref "C139") (pin "1") (pinfunction "1_1") (pintype "passive"))
      (node (ref "Q10") (pin "2") (pinfunction "2_2") (pintype "passive"))
      (node (ref "Q11") (pin "2") (pinfunction "2_2") (pintype "passive"))
      (node (ref "Q17") (pin "2") (pinfunction "2_2") (pintype "passive"))
      (node (ref "Q18") (pin "2") (pinfunction "2_2") (pintype "passive"))
      (node (ref "Q19") (pin "2") (pinfunction "2_2") (pintype "passive"))
      (node (ref "Q20") (pin "2") (pinfunction "2_2") (pintype "passive"))
      (node (ref "Q21") (pin "2") (pinfunction "2_2") (pintype "passive"))
      (node (ref "Q27") (pin "2") (pinfunction "2_2") (pintype "passive"))
      (node (ref "Q28") (pin "2") (pinfunction "2_2") (pintype "passive"))
      (node (ref "Q29") (pin "2") (pinfunction "2_2") (pintype "passive"))
      (node (ref "Q30") (pin "2") (pinfunction "2_2") (pintype "passive"))
      (node (ref "Q31") (pin "2") (pinfunction "2_2") (pintype "passive"))
      (node (ref "Q7") (pin "2") (pinfunction "2_2") (pintype "passive"))
      (node (ref "Q8") (pin "2") (pinfunction "2_2") (pintype "passive"))
      (node (ref "Q9") (pin "2") (pinfunction "2_2") (pintype "passive"))
      (node (ref "R141") (pin "1") (pinfunction "1_1") (pintype "passive"))
      (node (ref "R142") (pin "1") (pinfunction "1_1") (pintype "passive"))
      (node (ref "R143") (pin "1") (pinfunction "1_1") (pintype "passive"))
      (node (ref "R144") (pin "1") (pinfunction "1_1") (pintype "passive"))
      (node (ref "R145") (pin "1") (pinfunction "1_1") (pintype "passive"))
      (node (ref "R171") (pin "1") (pinfunction "1_1") (pintype "passive"))
      (node (ref "R172") (pin "1") (pinfunction "1_1") (pintype "passive"))
      (node (ref "R173") (pin "1") (pinfunction "1_1") (pintype "passive"))
      (node (ref "R174") (pin "1") (pinfunction "1_1") (pintype "passive"))
      (node (ref "R175") (pin "1") (pinfunction "1_1") (pintype "passive"))
      (node (ref "R201") (pin "1") (pinfunction "1_1") (pintype "passive"))
      (node (ref "R202") (pin "1") (pinfunction "1_1") (pintype "passive"))
      (node (ref "R203") (pin "1") (pinfunction "1_1") (pintype "passive"))
      (node (ref "R204") (pin "1") (pinfunction "1_1") (pintype "passive"))
      (node (ref "R205") (pin "1") (pinfunction "1_1") (pintype "passive"))
    )
    (net (code "9") (name "L1") (class "Default")
      (node (ref "D17") (pin "k") (pinfunction "k_k") (pintype "passive"))
      (node (ref "D18") (pin "k") (pinfunction "k_k") (pintype "passive"))
      (node (ref "D19") (pin "k") (pinfunction "k_k") (pintype "passive"))
      (node (ref "D20") (pin "k") (pinfunction "k_k") (pintype "passive"))
      (node (ref "D21") (pin "k") (pinfunction "k_k") (pintype "passive"))
      (node (ref "R132") (pin "1") (pinfunction "1_1") (pintype "passive"))
      (node (ref "R134") (pin "1") (pinfunction "1_1") (pintype "passive"))
      (node (ref "R136") (pin "1") (pinfunction "1_1") (pintype "passive"))
      (node (ref "R138") (pin "1") (pinfunction "1_1") (pintype "passive"))
      (node (ref "R140") (pin "1") (pinfunction "1_1") (pintype "passive"))
    )
    (net (code "10") (name "L2") (class "Default")
      (node (ref "D27") (pin "k") (pinfunction "k_k") (pintype "passive"))
      (node (ref "D28") (pin "k") (pinfunction "k_k") (pintype "passive"))
      (node (ref "D29") (pin "k") (pinfunction "k_k") (pintype "passive"))
      (node (ref "D30") (pin "k") (pinfunction "k_k") (pintype "passive"))
      (node (ref "D31") (pin "k") (pinfunction "k_k") (pintype "passive"))
      (node (ref "R162") (pin "1") (pinfunction "1_1") (pintype "passive"))
      (node (ref "R164") (pin "1") (pinfunction "1_1") (pintype "passive"))
      (node (ref "R166") (pin "1") (pinfunction "1_1") (pintype "passive"))
      (node (ref "R168") (pin "1") (pinfunction "1_1") (pintype "passive"))
      (node (ref "R170") (pin "1") (pinfunction "1_1") (pintype "passive"))
    )
    (net (code "11") (name "L3") (class "Default")
      (node (ref "D37") (pin "k") (pinfunction "k_k") (pintype "passive"))
      (node (ref "D38") (pin "k") (pinfunction "k_k") (pintype "passive"))
      (node (ref "D39") (pin "k") (pinfunction "k_k") (pintype "passive"))
      (node (ref "D40") (pin "k") (pinfunction "k_k") (pintype "passive"))
      (node (ref "D41") (pin "k") (pinfunction "k_k") (pintype "passive"))
      (node (ref "R192") (pin "1") (pinfunction "1_1") (pintype "passive"))
      (node (ref "R194") (pin "1") (pinfunction "1_1") (pintype "passive"))
      (node (ref "R196") (pin "1") (pinfunction "1_1") (pintype "passive"))
      (node (ref "R198") (pin "1") (pinfunction "1_1") (pintype "passive"))
      (node (ref "R200") (pin "1") (pinfunction "1_1") (pintype "passive"))
    )
    (net (code "12") (name "Net-(C128-Pad1)") (class "Default")
      (node (ref "C128") (pin "1") (pinfunction "1_1") (pintype "passive"))
      (node (ref "C129") (pin "2") (pinfunction "2_2") (pintype "passive"))
    )
    (net (code "13") (name "Net-(C128-Pad2)") (class "Default")
      (node (ref "C128") (pin "2") (pinfunction "2_2") (pintype "passive"))
      (node (ref "R219") (pin "1") (pinfunction "1_1") (pintype "passive"))
    )
    (net (code "14") (name "Net-(C129-Pad1)") (class "Default")
      (node (ref "C129") (pin "1") (pinfunction "1_1") (pintype "passive"))
      (node (ref "C130") (pin "2") (pinfunction "2_2") (pintype "passive"))
    )
    (net (code "15") (name "Net-(C130-Pad1)") (class "Default")
      (node (ref "C130") (pin "1") (pinfunction "1_1") (pintype "passive"))
      (node (ref "C131") (pin "2") (pinfunction "2_2") (pintype "passive"))
    )
    (net (code "16") (name "Net-(C132-Pad1)") (class "Default")
      (node (ref "C132") (pin "1") (pinfunction "1_1") (pintype "passive"))
      (node (ref "C133") (pin "2") (pinfunction "2_2") (pintype "passive"))
    )
    (net (code "17") (name "Net-(C132-Pad2)") (class "Default")
      (node (ref "C132") (pin "2") (pinfunction "2_2") (pintype "passive"))
      (node (ref "R220") (pin "1") (pinfunction "1_1") (pintype "passive"))
    )
    (net (code "18") (name "Net-(C133-Pad1)") (class "Default")
      (node (ref "C133") (pin "1") (pinfunction "1_1") (pintype "passive"))
      (node (ref "C134") (pin "2") (pinfunction "2_2") (pintype "passive"))
    )
    (net (code "19") (name "Net-(C134-Pad1)") (class "Default")
      (node (ref "C134") (pin "1") (pinfunction "1_1") (pintype "passive"))
      (node (ref "C135") (pin "2") (pinfunction "2_2") (pintype "passive"))
    )
    (net (code "20") (name "Net-(C136-Pad1)") (class "Default")
      (node (ref "C136") (pin "1") (pinfunction "1_1") (pintype "passive"))
      (node (ref "C137") (pin "2") (pinfunction "2_2") (pintype "passive"))
    )
    (net (code "21") (name "Net-(C136-Pad2)") (class "Default")
      (node (ref "C136") (pin "2") (pinfunction "2_2") (pintype "passive"))
      (node (ref "R221") (pin "1") (pinfunction "1_1") (pintype "passive"))
    )
    (net (code "22") (name "Net-(C137-Pad1)") (class "Default")
      (node (ref "C137") (pin "1") (pinfunction "1_1") (pintype "passive"))
      (node (ref "C138") (pin "2") (pinfunction "2_2") (pintype "passive"))
    )
    (net (code "23") (name "Net-(C138-Pad1)") (class "Default")
      (node (ref "C138") (pin "1") (pinfunction "1_1") (pintype "passive"))
      (node (ref "C139") (pin "2") (pinfunction "2_2") (pintype "passive"))
    )
    (net (code "24") (name "Net-(D12-Pada)") (class "Default")
      (node (ref "D12") (pin "a") (pinfunction "a_a") (pintype "passive"))
      (node (ref "R116") (pin "1") (pinfunction "1_1") (pintype "passive"))
    )
    (net (code "25") (name "Net-(D13-Pada)") (class "Default")
      (node (ref "D13") (pin "a") (pinfunction "a_a") (pintype "passive"))
      (node (ref "R118") (pin "1") (pinfunction "1_1") (pintype "passive"))
    )
    (net (code "26") (name "Net-(D14-Pada)") (class "Default")
      (node (ref "D14") (pin "a") (pinfunction "a_a") (pintype "passive"))
      (node (ref "R120") (pin "1") (pinfunction "1_1") (pintype "passive"))
    )
    (net (code "27") (name "Net-(D15-Pada)") (class "Default")
      (node (ref "D15") (pin "a") (pinfunction "a_a") (pintype "passive"))
      (node (ref "R122") (pin "1") (pinfunction "1_1") (pintype "passive"))
    )
    (net (code "28") (name "Net-(D16-Pada)") (class "Default")
      (node (ref "D16") (pin "a") (pinfunction "a_a") (pintype "passive"))
      (node (ref "R124") (pin "1") (pinfunction "1_1") (pintype "passive"))
    )
    (net (code "29") (name "Net-(D17-Pada)") (class "Default")
      (node (ref "D17") (pin "a") (pinfunction "a_a") (pintype "passive"))
      (node (ref "R131") (pin "1") (pinfunction "1_1") (pintype "passive"))
    )
    (net (code "30") (name "Net-(D18-Pada)") (class "Default")
      (node (ref "D18") (pin "a") (pinfunction "a_a") (pintype "passive"))
      (node (ref "R133") (pin "1") (pinfunction "1_1") (pintype "passive"))
    )
    (net (code "31") (name "Net-(D19-Pada)") (class "Default")
      (node (ref "D19") (pin "a") (pinfunction "a_a") (pintype "passive"))
      (node (ref "R135") (pin "1") (pinfunction "1_1") (pintype "passive"))
    )
    (net (code "32") (name "Net-(D20-Pada)") (class "Default")
      (node (ref "D20") (pin "a") (pinfunction "a_a") (pintype "passive"))
      (node (ref "R137") (pin "1") (pinfunction "1_1") (pintype "passive"))
    )
    (net (code "33") (name "Net-(D21-Pada)") (class "Default")
      (node (ref "D21") (pin "a") (pinfunction "a_a") (pintype "passive"))
      (node (ref "R139") (pin "1") (pinfunction "1_1") (pintype "passive"))
    )
    (net (code "34") (name "Net-(D22-Pada)") (class "Default")
      (node (ref "D22") (pin "a") (pinfunction "a_a") (pintype "passive"))
      (node (ref "R146") (pin "1") (pinfunction "1_1") (pintype "passive"))
    )
    (net (code "35") (name "Net-(D23-Pada)") (class "Default")
      (node (ref "D23") (pin "a") (pinfunction "a_a") (pintype "passive"))
      (node (ref "R148") (pin "1") (pinfunction "1_1") (pintype "passive"))
    )
    (net (code "36") (name "Net-(D24-Pada)") (class "Default")
      (node (ref "D24") (pin "a") (pinfunction "a_a") (pintype "passive"))
      (node (ref "R150") (pin "1") (pinfunction "1_1") (pintype "passive"))
    )
    (net (code "37") (name "Net-(D25-Pada)") (class "Default")
      (node (ref "D25") (pin "a") (pinfunction "a_a") (pintype "passive"))
      (node (ref "R152") (pin "1") (pinfunction "1_1") (pintype "passive"))
    )
    (net (code "38") (name "Net-(D26-Pada)") (class "Default")
      (node (ref "D26") (pin "a") (pinfunction "a_a") (pintype "passive"))
      (node (ref "R154") (pin "1") (pinfunction "1_1") (pintype "passive"))
    )
    (net (code "39") (name "Net-(D27-Pada)") (class "Default")
      (node (ref "D27") (pin "a") (pinfunction "a_a") (pintype "passive"))
      (node (ref "R161") (pin "1") (pinfunction "1_1") (pintype "passive"))
    )
    (net (code "40") (name "Net-(D28-Pada)") (class "Default")
      (node (ref "D28") (pin "a") (pinfunction "a_a") (pintype "passive"))
      (node (ref "R163") (pin "1") (pinfunction "1_1") (pintype "passive"))
    )
    (net (code "41") (name "Net-(D29-Pada)") (class "Default")
      (node (ref "D29") (pin "a") (pinfunction "a_a") (pintype "passive"))
      (node (ref "R165") (pin "1") (pinfunction "1_1") (pintype "passive"))
    )
    (net (code "42") (name "Net-(D30-Pada)") (class "Default")
      (node (ref "D30") (pin "a") (pinfunction "a_a") (pintype "passive"))
      (node (ref "R167") (pin "1") (pinfunction "1_1") (pintype "passive"))
    )
    (net (code "43") (name "Net-(D31-Pada)") (class "Default")
      (node (ref "D31") (pin "a") (pinfunction "a_a") (pintype "passive"))
      (node (ref "R169") (pin "1") (pinfunction "1_1") (pintype "passive"))
    )
    (net (code "44") (name "Net-(D32-Pada)") (class "Default")
      (node (ref "D32") (pin "a") (pinfunction "a_a") (pintype "passive"))
      (node (ref "R176") (pin "1") (pinfunction "1_1") (pintype "passive"))
    )
    (net (code "45") (name "Net-(D33-Pada)") (class "Default")
      (node (ref "D33") (pin "a") (pinfunction "a_a") (pintype "passive"))
      (node (ref "R178") (pin "1") (pinfunction "1_1") (pintype "passive"))
    )
    (net (code "46") (name "Net-(D34-Pada)") (class "Default")
      (node (ref "D34") (pin "a") (pinfunction "a_a") (pintype "passive"))
      (node (ref "R180") (pin "1") (pinfunction "1_1") (pintype "passive"))
    )
    (net (code "47") (name "Net-(D35-Pada)") (class "Default")
      (node (ref "D35") (pin "a") (pinfunction "a_a") (pintype "passive"))
      (node (ref "R182") (pin "1") (pinfunction "1_1") (pintype "passive"))
    )
    (net (code "48") (name "Net-(D36-Pada)") (class "Default")
      (node (ref "D36") (pin "a") (pinfunction "a_a") (pintype "passive"))
      (node (ref "R184") (pin "1") (pinfunction "1_1") (pintype "passive"))
    )
    (net (code "49") (name "Net-(D37-Pada)") (class "Default")
      (node (ref "D37") (pin "a") (pinfunction "a_a") (pintype "passive"))
      (node (ref "R191") (pin "1") (pinfunction "1_1") (pintype "passive"))
    )
    (net (code "50") (name "Net-(D38-Pada)") (class "Default")
      (node (ref "D38") (pin "a") (pinfunction "a_a") (pintype "passive"))
      (node (ref "R193") (pin "1") (pinfunction "1_1") (pintype "passive"))
    )
    (net (code "51") (name "Net-(D39-Pada)") (class "Default")
      (node (ref "D39") (pin "a") (pinfunction "a_a") (pintype "passive"))
      (node (ref "R195") (pin "1") (pinfunction "1_1") (pintype "passive"))
    )
    (net (code "52") (name "Net-(D40-Pada)") (class "Default")
      (node (ref "D40") (pin "a") (pinfunction "a_a") (pintype "passive"))
      (node (ref "R197") (pin "1") (pinfunction "1_1") (pintype "passive"))
    )
    (net (code "53") (name "Net-(D41-Pada)") (class "Default")
      (node (ref "D41") (pin "a") (pinfunction "a_a") (pintype "passive"))
      (node (ref "R199") (pin "1") (pinfunction "1_1") (pintype "passive"))
    )
    (net (code "54") (name "Net-(Q2-Pad1)") (class "Default")
      (node (ref "Q2") (pin "1") (pinfunction "1_1") (pintype "passive"))
      (node (ref "R116") (pin "2") (pinfunction "2_2") (pintype "passive"))
      (node (ref "R117") (pin "2") (pinfunction "2_2") (pintype "passive"))
      (node (ref "R126") (pin "2") (pinfunction "2_2") (pintype "passive"))
    )
    (net (code "55") (name "Net-(Q3-Pad1)") (class "Default")
      (node (ref "Q3") (pin "1") (pinfunction "1_1") (pintype "passive"))
      (node (ref "R118") (pin "2") (pinfunction "2_2") (pintype "passive"))
      (node (ref "R119") (pin "2") (pinfunction "2_2") (pintype "passive"))
      (node (ref "R127") (pin "2") (pinfunction "2_2") (pintype "passive"))
    )
    (net (code "56") (name "Net-(Q4-Pad1)") (class "Default")
      (node (ref "Q4") (pin "1") (pinfunction "1_1") (pintype "passive"))
      (node (ref "R120") (pin "2") (pinfunction "2_2") (pintype "passive"))
      (node (ref "R121") (pin "2") (pinfunction "2_2") (pintype "passive"))
      (node (ref "R128") (pin "2") (pinfunction "2_2") (pintype "passive"))
    )
    (net (code "57") (name "Net-(Q5-Pad1)") (class "Default")
      (node (ref "Q5") (pin "1") (pinfunction "1_1") (pintype "passive"))
      (node (ref "R122") (pin "2") (pinfunction "2_2") (pintype "passive"))
      (node (ref "R123") (pin "2") (pinfunction "2_2") (pintype "passive"))
      (node (ref "R129") (pin "2") (pinfunction "2_2") (pintype "passive"))
    )
    (net (code "58") (name "Net-(Q6-Pad1)") (class "Default")
      (node (ref "Q6") (pin "1") (pinfunction "1_1") (pintype "passive"))
      (node (ref "R124") (pin "2") (pinfunction "2_2") (pintype "passive"))
      (node (ref "R125") (pin "2") (pinfunction "2_2") (pintype "passive"))
      (node (ref "R130") (pin "2") (pinfunction "2_2") (pintype "passive"))
    )
    (net (code "59") (name "Net-(Q7-Pad1)") (class "Default")
      (node (ref "Q7") (pin "1") (pinfunction "1_1") (pintype "passive"))
      (node (ref "R131") (pin "2") (pinfunction "2_2") (pintype "passive"))
      (node (ref "R132") (pin "2") (pinfunction "2_2") (pintype "passive"))
      (node (ref "R141") (pin "2") (pinfunction "2_2") (pintype "passive"))
    )
    (net (code "60") (name "Net-(Q8-Pad1)") (class "Default")
      (node (ref "Q8") (pin "1") (pinfunction "1_1") (pintype "passive"))
      (node (ref "R133") (pin "2") (pinfunction "2_2") (pintype "passive"))
      (node (ref "R134") (pin "2") (pinfunction "2_2") (pintype "passive"))
      (node (ref "R142") (pin "2") (pinfunction "2_2") (pintype "passive"))
    )
    (net (code "61") (name "Net-(Q9-Pad1)") (class "Default")
      (node (ref "Q9") (pin "1") (pinfunction "1_1") (pintype "passive"))
      (node (ref "R135") (pin "2") (pinfunction "2_2") (pintype "passive"))
      (node (ref "R136") (pin "2") (pinfunction "2_2") (pintype "passive"))
      (node (ref "R143") (pin "2") (pinfunction "2_2") (pintype "passive"))
    )
    (net (code "62") (name "Net-(Q10-Pad1)") (class "Default")
      (node (ref "Q10") (pin "1") (pinfunction "1_1") (pintype "passive"))
      (node (ref "R137") (pin "2") (pinfunction "2_2") (pintype "passive"))
      (node (ref "R138") (pin "2") (pinfunction "2_2") (pintype "passive"))
      (node (ref "R144") (pin "2") (pinfunction "2_2") (pintype "passive"))
    )
    (net (code "63") (name "Net-(Q11-Pad1)") (class "Default")
      (node (ref "Q11") (pin "1") (pinfunction "1_1") (pintype "passive"))
      (node (ref "R139") (pin "2") (pinfunction "2_2") (pintype "passive"))
      (node (ref "R140") (pin "2") (pinfunction "2_2") (pintype "passive"))
      (node (ref "R145") (pin "2") (pinfunction "2_2") (pintype "passive"))
    )
    (net (code "64") (name "Net-(Q12-Pad1)") (class "Default")
      (node (ref "Q12") (pin "1") (pinfunction "1_1") (pintype "passive"))
      (node (ref "R146") (pin "2") (pinfunction "2_2") (pintype "passive"))
      (node (ref "R147") (pin "2") (pinfunction "2_2") (pintype "passive"))
      (node (ref "R156") (pin "2") (pinfunction "2_2") (pintype "passive"))
    )
    (net (code "65") (name "Net-(Q13-Pad1)") (class "Default")
      (node (ref "Q13") (pin "1") (pinfunction "1_1") (pintype "passive"))
      (node (ref "R148") (pin "2") (pinfunction "2_2") (pintype "passive"))
      (node (ref "R149") (pin "2") (pinfunction "2_2") (pintype "passive"))
      (node (ref "R157") (pin "2") (pinfunction "2_2") (pintype "passive"))
    )
    (net (code "66") (name "Net-(Q14-Pad1)") (class "Default")
      (node (ref "Q14") (pin "1") (pinfunction "1_1") (pintype "passive"))
      (node (ref "R150") (pin "2") (pinfunction "2_2") (pintype "passive"))
      (node (ref "R151") (pin "2") (pinfunction "2_2") (pintype "passive"))
      (node (ref "R158") (pin "2") (pinfunction "2_2") (pintype "passive"))
    )
    (net (code "67") (name "Net-(Q15-Pad1)") (class "Default")
      (node (ref "Q15") (pin "1") (pinfunction "1_1") (pintype "passive"))
      (node (ref "R152") (pin "2") (pinfunction "2_2") (pintype "passive"))
      (node (ref "R153") (pin "2") (pinfunction "2_2") (pintype "passive"))
      (node (ref "R159") (pin "2") (pinfunction "2_2") (pintype "passive"))
    )
    (net (code "68") (name "Net-(Q16-Pad1)") (class "Default")
      (node (ref "Q16") (pin "1") (pinfunction "1_1") (pintype "passive"))
      (node (ref "R154") (pin "2") (pinfunction "2_2") (pintype "passive"))
      (node (ref "R155") (pin "2") (pinfunction "2_2") (pintype "passive"))
      (node (ref "R160") (pin "2") (pinfunction "2_2") (pintype "passive"))
    )
    (net (code "69") (name "Net-(Q17-Pad1)") (class "Default")
      (node (ref "Q17") (pin "1") (pinfunction "1_1") (pintype "passive"))
      (node (ref "R161") (pin "2") (pinfunction "2_2") (pintype "passive"))
      (node (ref "R162") (pin "2") (pinfunction "2_2") (pintype "passive"))
      (node (ref "R171") (pin "2") (pinfunction "2_2") (pintype "passive"))
    )
    (net (code "70") (name "Net-(Q18-Pad1)") (class "Default")
      (node (ref "Q18") (pin "1") (pinfunction "1_1") (pintype "passive"))
      (node (ref "R163") (pin "2") (pinfunction "2_2") (pintype "passive"))
      (node (ref "R164") (pin "2") (pinfunction "2_2") (pintype "passive"))
      (node (ref "R172") (pin "2") (pinfunction "2_2") (pintype "passive"))
    )
    (net (code "71") (name "Net-(Q19-Pad1)") (class "Default")
      (node (ref "Q19") (pin "1") (pinfunction "1_1") (pintype "passive"))
      (node (ref "R165") (pin "2") (pinfunction "2_2") (pintype "passive"))
      (node (ref "R166") (pin "2") (pinfunction "2_2") (pintype "passive"))
      (node (ref "R173") (pin "2") (pinfunction "2_2") (pintype "passive"))
    )
    (net (code "72") (name "Net-(Q20-Pad1)") (class "Default")
      (node (ref "Q20") (pin "1") (pinfunction "1_1") (pintype "passive"))
      (node (ref "R167") (pin "2") (pinfunction "2_2") (pintype "passive"))
      (node (ref "R168") (pin "2") (pinfunction "2_2") (pintype "passive"))
      (node (ref "R174") (pin "2") (pinfunction "2_2") (pintype "passive"))
    )
    (net (code "73") (name "Net-(Q21-Pad1)") (class "Default")
      (node (ref "Q21") (pin "1") (pinfunction "1_1") (pintype "passive"))
      (node (ref "R169") (pin "2") (pinfunction "2_2") (pintype "passive"))
      (node (ref "R170") (pin "2") (pinfunction "2_2") (pintype "passive"))
      (node (ref "R175") (pin "2") (pinfunction "2_2") (pintype "passive"))
    )
    (net (code "74") (name "Net-(Q22-Pad1)") (class "Default")
      (node (ref "Q22") (pin "1") (pinfunction "1_1") (pintype "passive"))
      (node (ref "R176") (pin "2") (pinfunction "2_2") (pintype "passive"))
      (node (ref "R177") (pin "2") (pinfunction "2_2") (pintype "passive"))
      (node (ref "R186") (pin "2") (pinfunction "2_2") (pintype "passive"))
    )
    (net (code "75") (name "Net-(Q23-Pad1)") (class "Default")
      (node (ref "Q23") (pin "1") (pinfunction "1_1") (pintype "passive"))
      (node (ref "R178") (pin "2") (pinfunction "2_2") (pintype "passive"))
      (node (ref "R179") (pin "2") (pinfunction "2_2") (pintype "passive"))
      (node (ref "R187") (pin "2") (pinfunction "2_2") (pintype "passive"))
    )
    (net (code "76") (name "Net-(Q24-Pad1)") (class "Default")
      (node (ref "Q24") (pin "1") (pinfunction "1_1") (pintype "passive"))
      (node (ref "R180") (pin "2") (pinfunction "2_2") (pintype "passive"))
      (node (ref "R181") (pin "2") (pinfunction "2_2") (pintype "passive"))
      (node (ref "R188") (pin "2") (pinfunction "2_2") (pintype "passive"))
    )
    (net (code "77") (name "Net-(Q25-Pad1)") (class "Default")
      (node (ref "Q25") (pin "1") (pinfunction "1_1") (pintype "passive"))
      (node (ref "R182") (pin "2") (pinfunction "2_2") (pintype "passive"))
      (node (ref "R183") (pin "2") (pinfunction "2_2") (pintype "passive"))
      (node (ref "R189") (pin "2") (pinfunction "2_2") (pintype "passive"))
    )
    (net (code "78") (name "Net-(Q26-Pad1)") (class "Default")
      (node (ref "Q26") (pin "1") (pinfunction "1_1") (pintype "passive"))
      (node (ref "R184") (pin "2") (pinfunction "2_2") (pintype "passive"))
      (node (ref "R185") (pin "2") (pinfunction "2_2") (pintype "passive"))
      (node (ref "R190") (pin "2") (pinfunction "2_2") (pintype "passive"))
    )
    (net (code "79") (name "Net-(Q27-Pad1)") (class "Default")
      (node (ref "Q27") (pin "1") (pinfunction "1_1") (pintype "passive"))
      (node (ref "R191") (pin "2") (pinfunction "2_2") (pintype "passive"))
      (node (ref "R192") (pin "2") (pinfunction "2_2") (pintype "passive"))
      (node (ref "R201") (pin "2") (pinfunction "2_2") (pintype "passive"))
    )
    (net (code "80") (name "Net-(Q28-Pad1)") (class "Default")
      (node (ref "Q28") (pin "1") (pinfunction "1_1") (pintype "passive"))
      (node (ref "R193") (pin "2") (pinfunction "2_2") (pintype "passive"))
      (node (ref "R194") (pin "2") (pinfunction "2_2") (pintype "passive"))
      (node (ref "R202") (pin "2") (pinfunction "2_2") (pintype "passive"))
    )
    (net (code "81") (name "Net-(Q29-Pad1)") (class "Default")
      (node (ref "Q29") (pin "1") (pinfunction "1_1") (pintype "passive"))
      (node (ref "R195") (pin "2") (pinfunction "2_2") (pintype "passive"))
      (node (ref "R196") (pin "2") (pinfunction "2_2") (pintype "passive"))
      (node (ref "R203") (pin "2") (pinfunction "2_2") (pintype "passive"))
    )
    (net (code "82") (name "Net-(Q30-Pad1)") (class "Default")
      (node (ref "Q30") (pin "1") (pinfunction "1_1") (pintype "passive"))
      (node (ref "R197") (pin "2") (pinfunction "2_2") (pintype "passive"))
      (node (ref "R198") (pin "2") (pinfunction "2_2") (pintype "passive"))
      (node (ref "R204") (pin "2") (pinfunction "2_2") (pintype "passive"))
    )
    (net (code "83") (name "Net-(Q31-Pad1)") (class "Default")
      (node (ref "Q31") (pin "1") (pinfunction "1_1") (pintype "passive"))
      (node (ref "R199") (pin "2") (pinfunction "2_2") (pintype "passive"))
      (node (ref "R200") (pin "2") (pinfunction "2_2") (pintype "passive"))
      (node (ref "R205") (pin "2") (pinfunction "2_2") (pintype "passive"))
    )
    (net (code "84") (name "SourceH") (class "Default")
      (node (ref "Q2") (pin "2") (pinfunction "2_2") (pintype "passive"))
      (node (ref "Q3") (pin "2") (pinfunction "2_2") (pintype "passive"))
      (node (ref "Q4") (pin "2") (pinfunction "2_2") (pintype "passive"))
      (node (ref "Q5") (pin "2") (pinfunction "2_2") (pintype "passive"))
      (node (ref "Q6") (pin "2") (pinfunction "2_2") (pintype "passive"))
      (node (ref "R126") (pin "1") (pinfunction "1_1") (pintype "passive"))
      (node (ref "R127") (pin "1") (pinfunction "1_1") (pintype "passive"))
      (node (ref "R128") (pin "1") (pinfunction "1_1") (pintype "passive"))
      (node (ref "R129") (pin "1") (pinfunction "1_1") (pintype "passive"))
      (node (ref "R130") (pin "1") (pinfunction "1_1") (pintype "passive"))
    )
    (net (code "85") (name "SourceH1") (class "Default")
      (node (ref "Q12") (pin "2") (pinfunction "2_2") (pintype "passive"))
      (node (ref "Q13") (pin "2") (pinfunction "2_2") (pintype "passive"))
      (node (ref "Q14") (pin "2") (pinfunction "2_2") (pintype "passive"))
      (node (ref "Q15") (pin "2") (pinfunction "2_2") (pintype "passive"))
      (node (ref "Q16") (pin "2") (pinfunction "2_2") (pintype "passive"))
      (node (ref "R156") (pin "1") (pinfunction "1_1") (pintype "passive"))
      (node (ref "R157") (pin "1") (pinfunction "1_1") (pintype "passive"))
      (node (ref "R158") (pin "1") (pinfunction "1_1") (pintype "passive"))
      (node (ref "R159") (pin "1") (pinfunction "1_1") (pintype "passive"))
      (node (ref "R160") (pin "1") (pinfunction "1_1") (pintype "passive"))
    )
    (net (code "86") (name "unconnected-(C131-Pad1)") (class "Default")
      (node (ref "C131") (pin "1") (pinfunction "1_1") (pintype "passive"))
    )
  )
)
